# LickSense_v0_2.net
KiCad netlist of a schematic drawn in EAGLE
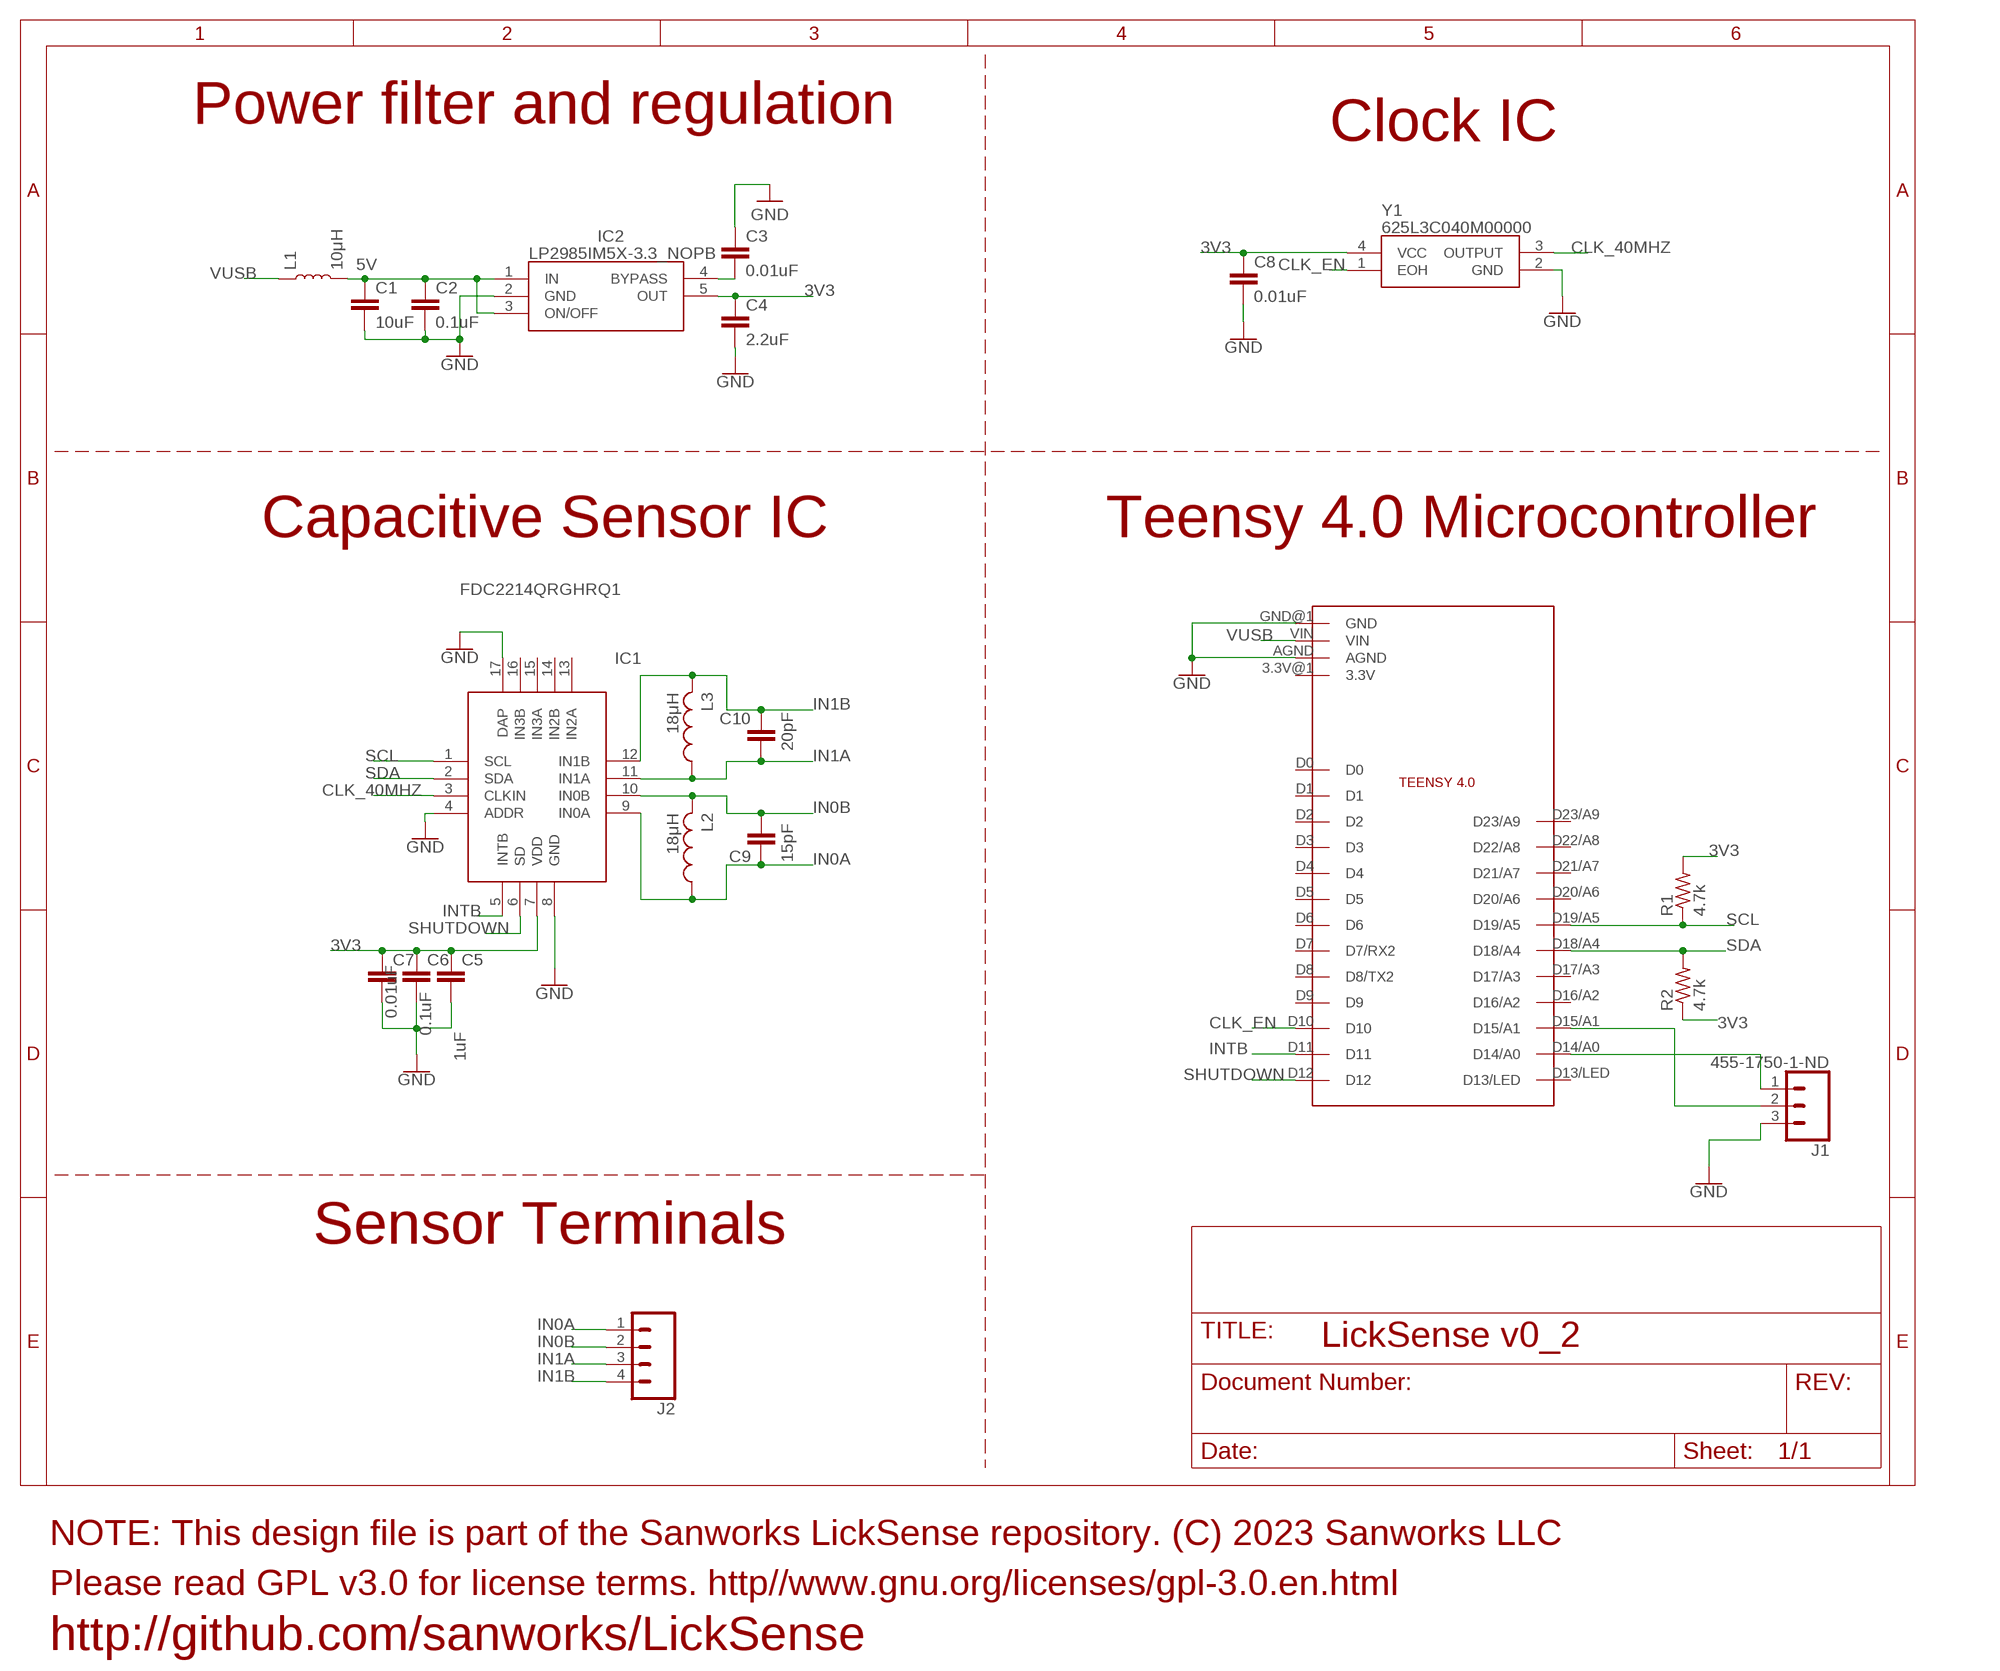
[diagram p0: schematic, sheet 1]

(export (version "E")
  (design (tool "Eeschema 10.0.6"))
  (components
    (comp (ref "C1")
      (value "10uF")
      (footprint "eagle-import:0805")
      (libsource (lib "eagle-import") (part "10UF-0805-10V-10%"))
    )
    (comp (ref "C2")
      (value "0.1uF")
      (footprint "eagle-import:0805")
      (libsource (lib "eagle-import") (part "1.0UF-0805-25V-(+80/-20%)"))
    )
    (comp (ref "C3")
      (value "0.01uF")
      (footprint "eagle-import:0805")
      (libsource (lib "eagle-import") (part "1.0UF-0805-25V-(+80/-20%)"))
    )
    (comp (ref "C4")
      (value "2.2uF")
      (footprint "eagle-import:0805")
      (libsource (lib "eagle-import") (part "1.0UF-0805-25V-(+80/-20%)"))
    )
    (comp (ref "C5")
      (value "1uF")
      (footprint "eagle-import:0805")
      (libsource (lib "eagle-import") (part "1.0UF-0805-25V-(+80/-20%)"))
    )
    (comp (ref "C6")
      (value "0.1uF")
      (footprint "eagle-import:0805")
      (libsource (lib "eagle-import") (part "1.0UF-0805-25V-(+80/-20%)"))
    )
    (comp (ref "C7")
      (value "0.01uF")
      (footprint "eagle-import:0805")
      (libsource (lib "eagle-import") (part "1.0UF-0805-25V-(+80/-20%)"))
    )
    (comp (ref "C8")
      (value "0.01uF")
      (footprint "eagle-import:0805")
      (libsource (lib "eagle-import") (part "1.0UF-0805-25V-(+80/-20%)"))
    )
    (comp (ref "C9")
      (value "15pF")
      (footprint "eagle-import:0805")
      (libsource (lib "eagle-import") (part "1.0UF-0805-25V-(+80/-20%)"))
    )
    (comp (ref "C10")
      (value "20pF")
      (footprint "eagle-import:0805")
      (libsource (lib "eagle-import") (part "1.0UF-0805-25V-(+80/-20%)"))
    )
    (comp (ref "IC1")
      (value "FDC2214QRGHRQ1")
      (footprint "eagle-import:QFN50P400X400X80-17N")
      (fields (field (name "MOUSER_PART_NUMBER") "595-FDC2214QRGHRQ1"))
      (libsource (lib "eagle-import") (part "FDC2214QRGHRQ1"))
    )
    (comp (ref "IC2")
      (value "LP2985IM5X-3.3_NOPB")
      (footprint "eagle-import:SOT95P280X145-5N")
      (fields
        (field (name "MANUFACTURER_PART_NUMBER") "LP2985IM5X-3.3/NOPB")
        (field (name "MOUSER_PART_NUMBER") "926-LP2985IM5X33NOPB")
      )
      (libsource (lib "eagle-import") (part "LP2985IM5X-3.3_NOPB"))
    )
    (comp (ref "J1")
      (value "455-1750-1-ND")
      (footprint "eagle-import:1X03")
      (libsource (lib "eagle-import") (part "CONN_03"))
    )
    (comp (ref "J2")
      (value "CONN_04PTH")
      (footprint "eagle-import:1X04")
      (libsource (lib "eagle-import") (part "CONN_04PTH"))
    )
    (comp (ref "L1")
      (value "10μH")
      (footprint "eagle-import:0806")
      (libsource (lib "eagle-import") (part "2.2μH_SHIELDED_INDUCTOR"))
    )
    (comp (ref "L2")
      (value "18μH")
      (footprint "eagle-import:L3225P")
      (libsource (lib "eagle-import") (part "L-USL3225P"))
    )
    (comp (ref "L3")
      (value "18μH")
      (footprint "eagle-import:L3225P")
      (libsource (lib "eagle-import") (part "L-USL3225P"))
    )
    (comp (ref "MC1")
      (value "TEENSY4.0_SIMPLE_NO_VUSB")
      (footprint "eagle-import:TEENSY4.0_SIMPLE_NO_VUSB")
      (libsource (lib "eagle-import") (part "TEENSY4.0_SIMPLE_NO_VUSB"))
    )
    (comp (ref "R1")
      (value "4.7k")
      (footprint "eagle-import:R0805")
      (libsource (lib "eagle-import") (part "R-US_R0805"))
    )
    (comp (ref "R2")
      (value "4.7k")
      (footprint "eagle-import:R0805")
      (libsource (lib "eagle-import") (part "R-US_R0805"))
    )
    (comp (ref "Y1")
      (value "625L3C040M00000")
      (footprint "eagle-import:625L3C040M00000")
      (fields (field (name "MOUSER_PART_NUMBER") "774-625L3C040M00000"))
      (libsource (lib "eagle-import") (part "625L3C040M00000"))
    )
  )
  (nets
    (net (code "1") (name "/3V3") (class "Default")
      (node (ref "C4") (pin "1") (pinfunction "1_1") (pintype "passive"))
      (node (ref "C5") (pin "1") (pinfunction "1_1") (pintype "passive"))
      (node (ref "C6") (pin "1") (pinfunction "1_1") (pintype "passive"))
      (node (ref "C7") (pin "1") (pinfunction "1_1") (pintype "passive"))
      (node (ref "C8") (pin "1") (pinfunction "1_1") (pintype "passive"))
      (node (ref "IC1") (pin "7") (pinfunction "VDD_7") (pintype "bidirectional"))
      (node (ref "IC2") (pin "5") (pinfunction "OUT_5") (pintype "bidirectional"))
      (node (ref "R1") (pin "2") (pinfunction "2_2") (pintype "passive"))
      (node (ref "R2") (pin "1") (pinfunction "1_1") (pintype "passive"))
      (node (ref "Y1") (pin "4") (pinfunction "VCC_4") (pintype "bidirectional"))
    )
    (net (code "2") (name "/5V") (class "Default")
      (node (ref "C1") (pin "1") (pinfunction "1_1") (pintype "passive"))
      (node (ref "C2") (pin "1") (pinfunction "1_1") (pintype "passive"))
      (node (ref "IC2") (pin "1") (pinfunction "IN_1") (pintype "bidirectional"))
      (node (ref "IC2") (pin "3") (pinfunction "ON/OFF_3") (pintype "bidirectional"))
      (node (ref "L1") (pin "2") (pinfunction "2_2") (pintype "passive"))
    )
    (net (code "3") (name "/CLK_40MHZ") (class "Default")
      (node (ref "IC1") (pin "3") (pinfunction "CLKIN_3") (pintype "bidirectional"))
      (node (ref "Y1") (pin "3") (pinfunction "OUTPUT_3") (pintype "bidirectional"))
    )
    (net (code "4") (name "/CLK_EN") (class "Default")
      (node (ref "MC1") (pin "D10") (pinfunction "D10_D10") (pintype "bidirectional"))
      (node (ref "Y1") (pin "1") (pinfunction "EOH_1") (pintype "bidirectional"))
    )
    (net (code "5") (name "/IN0A") (class "Default")
      (node (ref "C9") (pin "1") (pinfunction "1_1") (pintype "passive"))
      (node (ref "IC1") (pin "9") (pinfunction "IN0A_9") (pintype "bidirectional"))
      (node (ref "J2") (pin "1") (pinfunction "1_1") (pintype "passive"))
      (node (ref "L2") (pin "1") (pinfunction "1_1") (pintype "passive"))
    )
    (net (code "6") (name "/IN0B") (class "Default")
      (node (ref "C9") (pin "2") (pinfunction "2_2") (pintype "passive"))
      (node (ref "IC1") (pin "10") (pinfunction "IN0B_10") (pintype "bidirectional"))
      (node (ref "J2") (pin "2") (pinfunction "2_2") (pintype "passive"))
      (node (ref "L2") (pin "2") (pinfunction "2_2") (pintype "passive"))
    )
    (net (code "7") (name "/IN1A") (class "Default")
      (node (ref "C10") (pin "1") (pinfunction "1_1") (pintype "passive"))
      (node (ref "IC1") (pin "11") (pinfunction "IN1A_11") (pintype "bidirectional"))
      (node (ref "J2") (pin "3") (pinfunction "3_3") (pintype "passive"))
      (node (ref "L3") (pin "1") (pinfunction "1_1") (pintype "passive"))
    )
    (net (code "8") (name "/IN1B") (class "Default")
      (node (ref "C10") (pin "2") (pinfunction "2_2") (pintype "passive"))
      (node (ref "IC1") (pin "12") (pinfunction "IN1B_12") (pintype "bidirectional"))
      (node (ref "J2") (pin "4") (pinfunction "4_4") (pintype "passive"))
      (node (ref "L3") (pin "2") (pinfunction "2_2") (pintype "passive"))
    )
    (net (code "9") (name "/INTB") (class "Default")
      (node (ref "IC1") (pin "5") (pinfunction "INTB_5") (pintype "bidirectional"))
      (node (ref "MC1") (pin "D11") (pinfunction "D11_D11") (pintype "bidirectional"))
    )
    (net (code "10") (name "/SCL") (class "Default")
      (node (ref "IC1") (pin "1") (pinfunction "SCL_1") (pintype "bidirectional"))
      (node (ref "MC1") (pin "D19/A5") (pinfunction "D19/A5_D19/A5") (pintype "bidirectional"))
      (node (ref "R1") (pin "1") (pinfunction "1_1") (pintype "passive"))
    )
    (net (code "11") (name "/SDA") (class "Default")
      (node (ref "IC1") (pin "2") (pinfunction "SDA_2") (pintype "bidirectional"))
      (node (ref "MC1") (pin "D18/A4") (pinfunction "D18/A4_D18/A4") (pintype "bidirectional"))
      (node (ref "R2") (pin "2") (pinfunction "2_2") (pintype "passive"))
    )
    (net (code "12") (name "/SHUTDOWN") (class "Default")
      (node (ref "IC1") (pin "6") (pinfunction "SD_6") (pintype "bidirectional"))
      (node (ref "MC1") (pin "D12") (pinfunction "D12_D12") (pintype "bidirectional"))
    )
    (net (code "13") (name "/VUSB") (class "Default")
      (node (ref "L1") (pin "1") (pinfunction "1_1") (pintype "passive"))
      (node (ref "MC1") (pin "VIN") (pinfunction "VIN_VIN") (pintype "bidirectional"))
    )
    (net (code "14") (name "GND") (class "Default")
      (node (ref "C1") (pin "2") (pinfunction "2_2") (pintype "passive"))
      (node (ref "C2") (pin "2") (pinfunction "2_2") (pintype "passive"))
      (node (ref "C3") (pin "1") (pinfunction "1_1") (pintype "passive"))
      (node (ref "C4") (pin "2") (pinfunction "2_2") (pintype "passive"))
      (node (ref "C5") (pin "2") (pinfunction "2_2") (pintype "passive"))
      (node (ref "C6") (pin "2") (pinfunction "2_2") (pintype "passive"))
      (node (ref "C7") (pin "2") (pinfunction "2_2") (pintype "passive"))
      (node (ref "C8") (pin "2") (pinfunction "2_2") (pintype "passive"))
      (node (ref "IC1") (pin "17") (pinfunction "DAP_17") (pintype "bidirectional"))
      (node (ref "IC1") (pin "4") (pinfunction "ADDR_4") (pintype "bidirectional"))
      (node (ref "IC1") (pin "8") (pinfunction "GND_8") (pintype "bidirectional"))
      (node (ref "IC2") (pin "2") (pinfunction "GND_2") (pintype "bidirectional"))
      (node (ref "J1") (pin "3") (pinfunction "3_3") (pintype "passive"))
      (node (ref "MC1") (pin "AGND") (pinfunction "AGND_AGND") (pintype "bidirectional"))
      (node (ref "MC1") (pin "GND@1") (pinfunction "GND_GND@1") (pintype "bidirectional"))
      (node (ref "Y1") (pin "2") (pinfunction "GND_2") (pintype "bidirectional"))
    )
    (net (code "15") (name "Net-(IC2-BYPASS)") (class "Default")
      (node (ref "C3") (pin "2") (pinfunction "2_2") (pintype "passive"))
      (node (ref "IC2") (pin "4") (pinfunction "BYPASS_4") (pintype "bidirectional"))
    )
    (net (code "16") (name "Net-(J1-Pad1)") (class "Default")
      (node (ref "J1") (pin "1") (pinfunction "1_1") (pintype "passive"))
      (node (ref "MC1") (pin "D14/A0") (pinfunction "D14/A0_D14/A0") (pintype "bidirectional"))
    )
    (net (code "17") (name "Net-(J1-Pad2)") (class "Default")
      (node (ref "J1") (pin "2") (pinfunction "2_2") (pintype "passive"))
      (node (ref "MC1") (pin "D15/A1") (pinfunction "D15/A1_D15/A1") (pintype "bidirectional"))
    )
    (net (code "18") (name "unconnected-(IC1-IN2A-Pad13)") (class "Default")
      (node (ref "IC1") (pin "13") (pinfunction "IN2A_13") (pintype "bidirectional"))
    )
    (net (code "19") (name "unconnected-(IC1-IN2B-Pad14)") (class "Default")
      (node (ref "IC1") (pin "14") (pinfunction "IN2B_14") (pintype "bidirectional"))
    )
    (net (code "20") (name "unconnected-(IC1-IN3A-Pad15)") (class "Default")
      (node (ref "IC1") (pin "15") (pinfunction "IN3A_15") (pintype "bidirectional"))
    )
    (net (code "21") (name "unconnected-(IC1-IN3B-Pad16)") (class "Default")
      (node (ref "IC1") (pin "16") (pinfunction "IN3B_16") (pintype "bidirectional"))
    )
    (net (code "22") (name "unconnected-(MC1-3.3V-Pad3.3V@1)") (class "Default")
      (node (ref "MC1") (pin "3.3V@1") (pinfunction "3.3V_3.3V@1") (pintype "bidirectional"))
    )
    (net (code "23") (name "unconnected-(MC1-D7{slash}RX2-PadD7)") (class "Default")
      (node (ref "MC1") (pin "D7") (pinfunction "D7/RX2_D7") (pintype "bidirectional"))
    )
    (net (code "24") (name "unconnected-(MC1-D8{slash}TX2-PadD8)") (class "Default")
      (node (ref "MC1") (pin "D8") (pinfunction "D8/TX2_D8") (pintype "bidirectional"))
    )
    (net (code "25") (name "unconnected-(MC1-PadD0)") (class "Default")
      (node (ref "MC1") (pin "D0") (pinfunction "D0_D0") (pintype "bidirectional"))
    )
    (net (code "26") (name "unconnected-(MC1-PadD1)") (class "Default")
      (node (ref "MC1") (pin "D1") (pinfunction "D1_D1") (pintype "bidirectional"))
    )
    (net (code "27") (name "unconnected-(MC1-PadD2)") (class "Default")
      (node (ref "MC1") (pin "D2") (pinfunction "D2_D2") (pintype "bidirectional"))
    )
    (net (code "28") (name "unconnected-(MC1-PadD3)") (class "Default")
      (node (ref "MC1") (pin "D3") (pinfunction "D3_D3") (pintype "bidirectional"))
    )
    (net (code "29") (name "unconnected-(MC1-PadD4)") (class "Default")
      (node (ref "MC1") (pin "D4") (pinfunction "D4_D4") (pintype "bidirectional"))
    )
    (net (code "30") (name "unconnected-(MC1-PadD5)") (class "Default")
      (node (ref "MC1") (pin "D5") (pinfunction "D5_D5") (pintype "bidirectional"))
    )
    (net (code "31") (name "unconnected-(MC1-PadD6)") (class "Default")
      (node (ref "MC1") (pin "D6") (pinfunction "D6_D6") (pintype "bidirectional"))
    )
    (net (code "32") (name "unconnected-(MC1-PadD9)") (class "Default")
      (node (ref "MC1") (pin "D9") (pinfunction "D9_D9") (pintype "bidirectional"))
    )
    (net (code "33") (name "unconnected-(MC1-PadD13{slash}LED)") (class "Default")
      (node (ref "MC1") (pin "D13/LED") (pinfunction "D13/LED_D13/LED") (pintype "bidirectional"))
    )
    (net (code "34") (name "unconnected-(MC1-PadD16{slash}A2)") (class "Default")
      (node (ref "MC1") (pin "D16/A2") (pinfunction "D16/A2_D16/A2") (pintype "bidirectional"))
    )
    (net (code "35") (name "unconnected-(MC1-PadD17{slash}A3)") (class "Default")
      (node (ref "MC1") (pin "D17/A3") (pinfunction "D17/A3_D17/A3") (pintype "bidirectional"))
    )
    (net (code "36") (name "unconnected-(MC1-PadD20{slash}A6)") (class "Default")
      (node (ref "MC1") (pin "D20/A6") (pinfunction "D20/A6_D20/A6") (pintype "bidirectional"))
    )
    (net (code "37") (name "unconnected-(MC1-PadD21{slash}A7)") (class "Default")
      (node (ref "MC1") (pin "D21/A7") (pinfunction "D21/A7_D21/A7") (pintype "bidirectional"))
    )
    (net (code "38") (name "unconnected-(MC1-PadD22{slash}A8)") (class "Default")
      (node (ref "MC1") (pin "D22/A8") (pinfunction "D22/A8_D22/A8") (pintype "bidirectional"))
    )
    (net (code "39") (name "unconnected-(MC1-PadD23{slash}A9)") (class "Default")
      (node (ref "MC1") (pin "D23/A9") (pinfunction "D23/A9_D23/A9") (pintype "bidirectional"))
    )
  )
)
